# ma_esquema.net
KiCad netlist of a schematic drawn in EAGLE
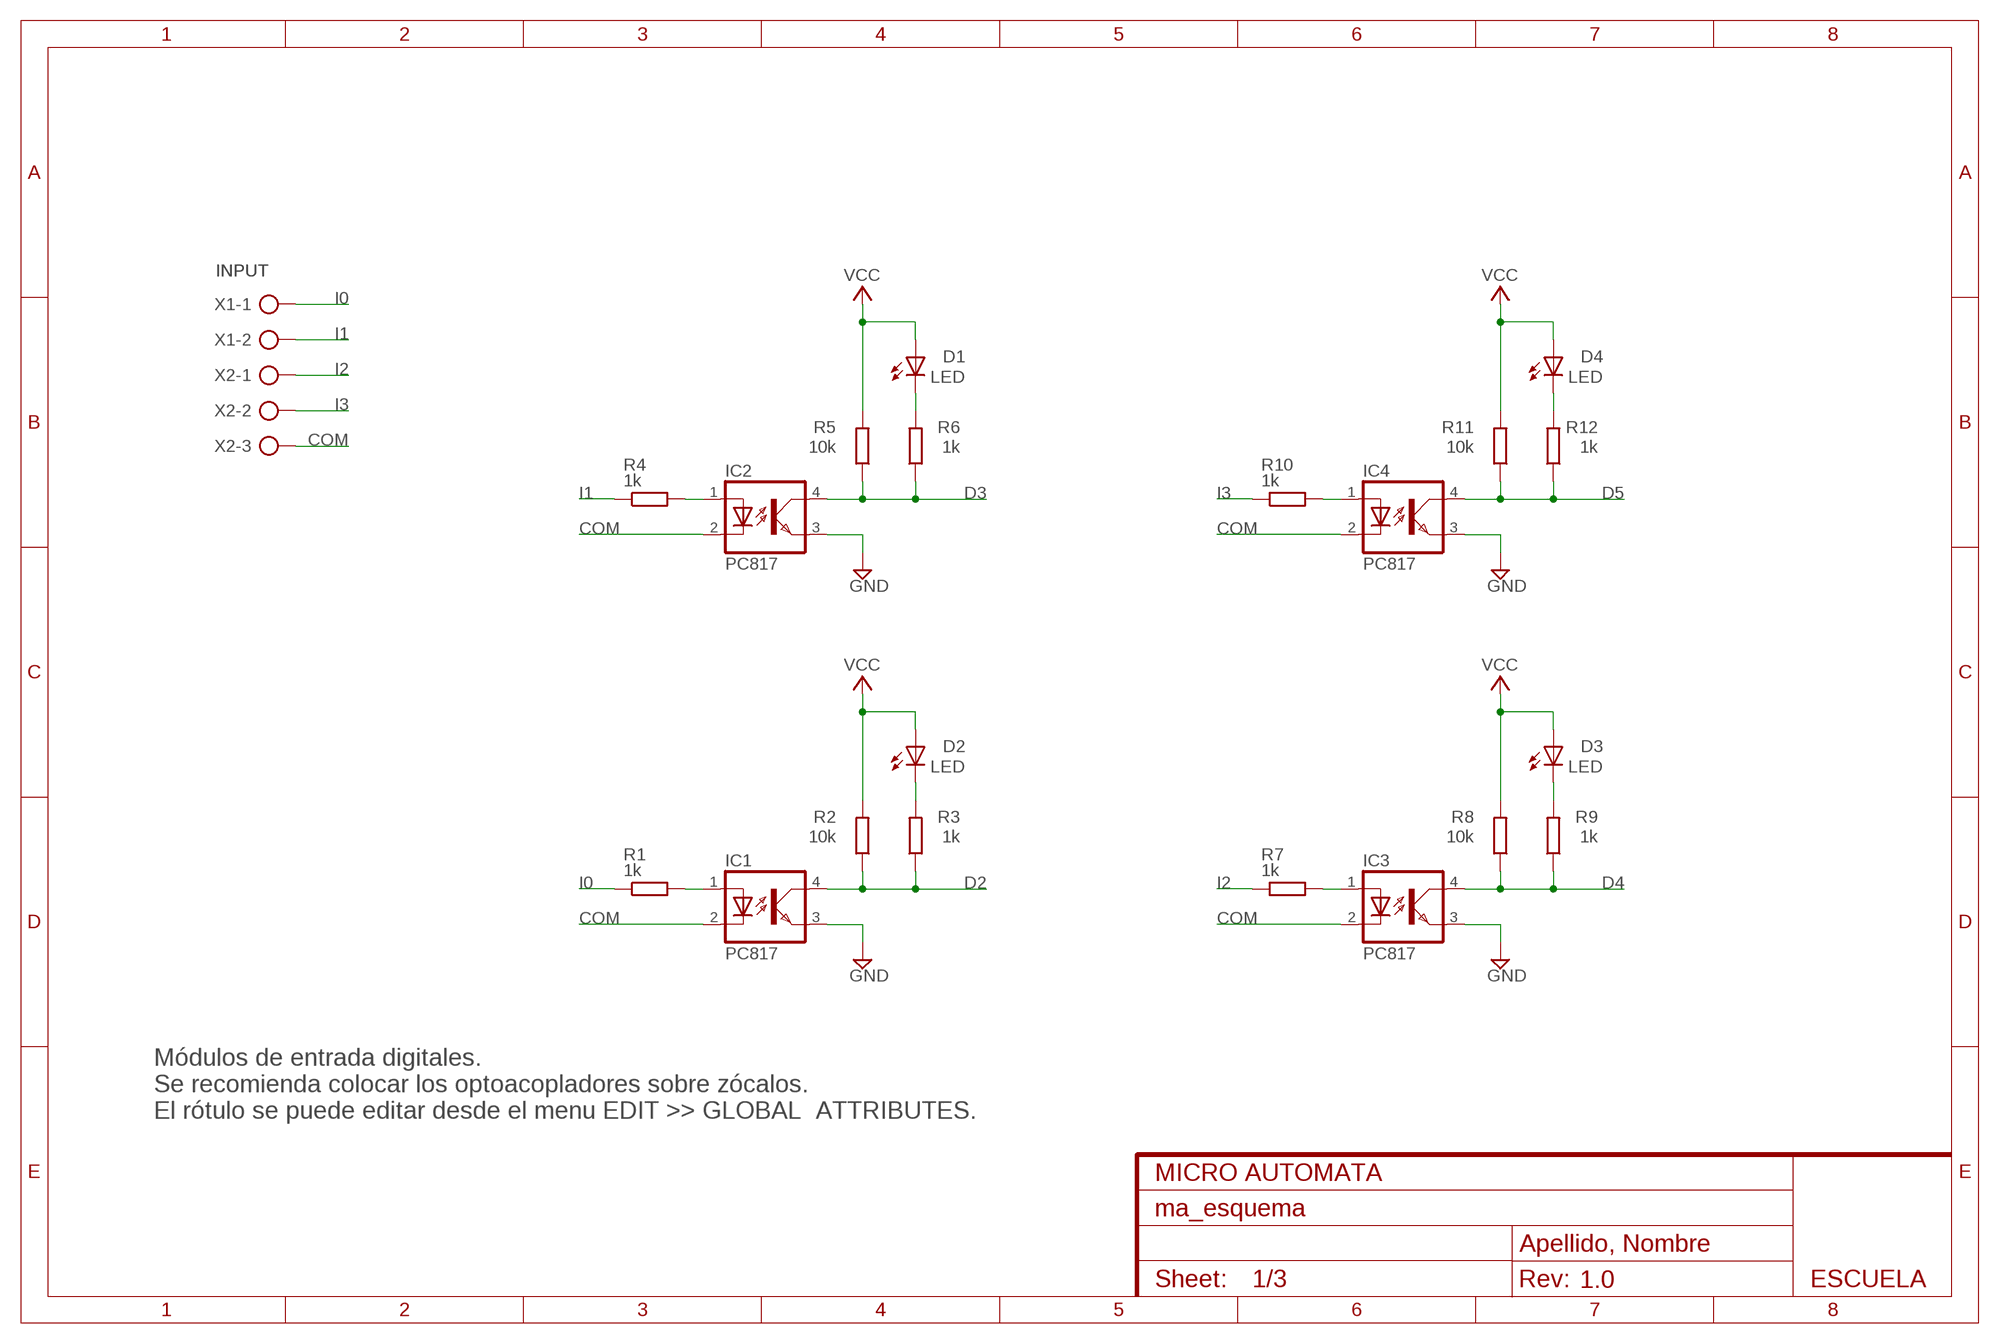
[diagram p0: schematic, sheet 1]
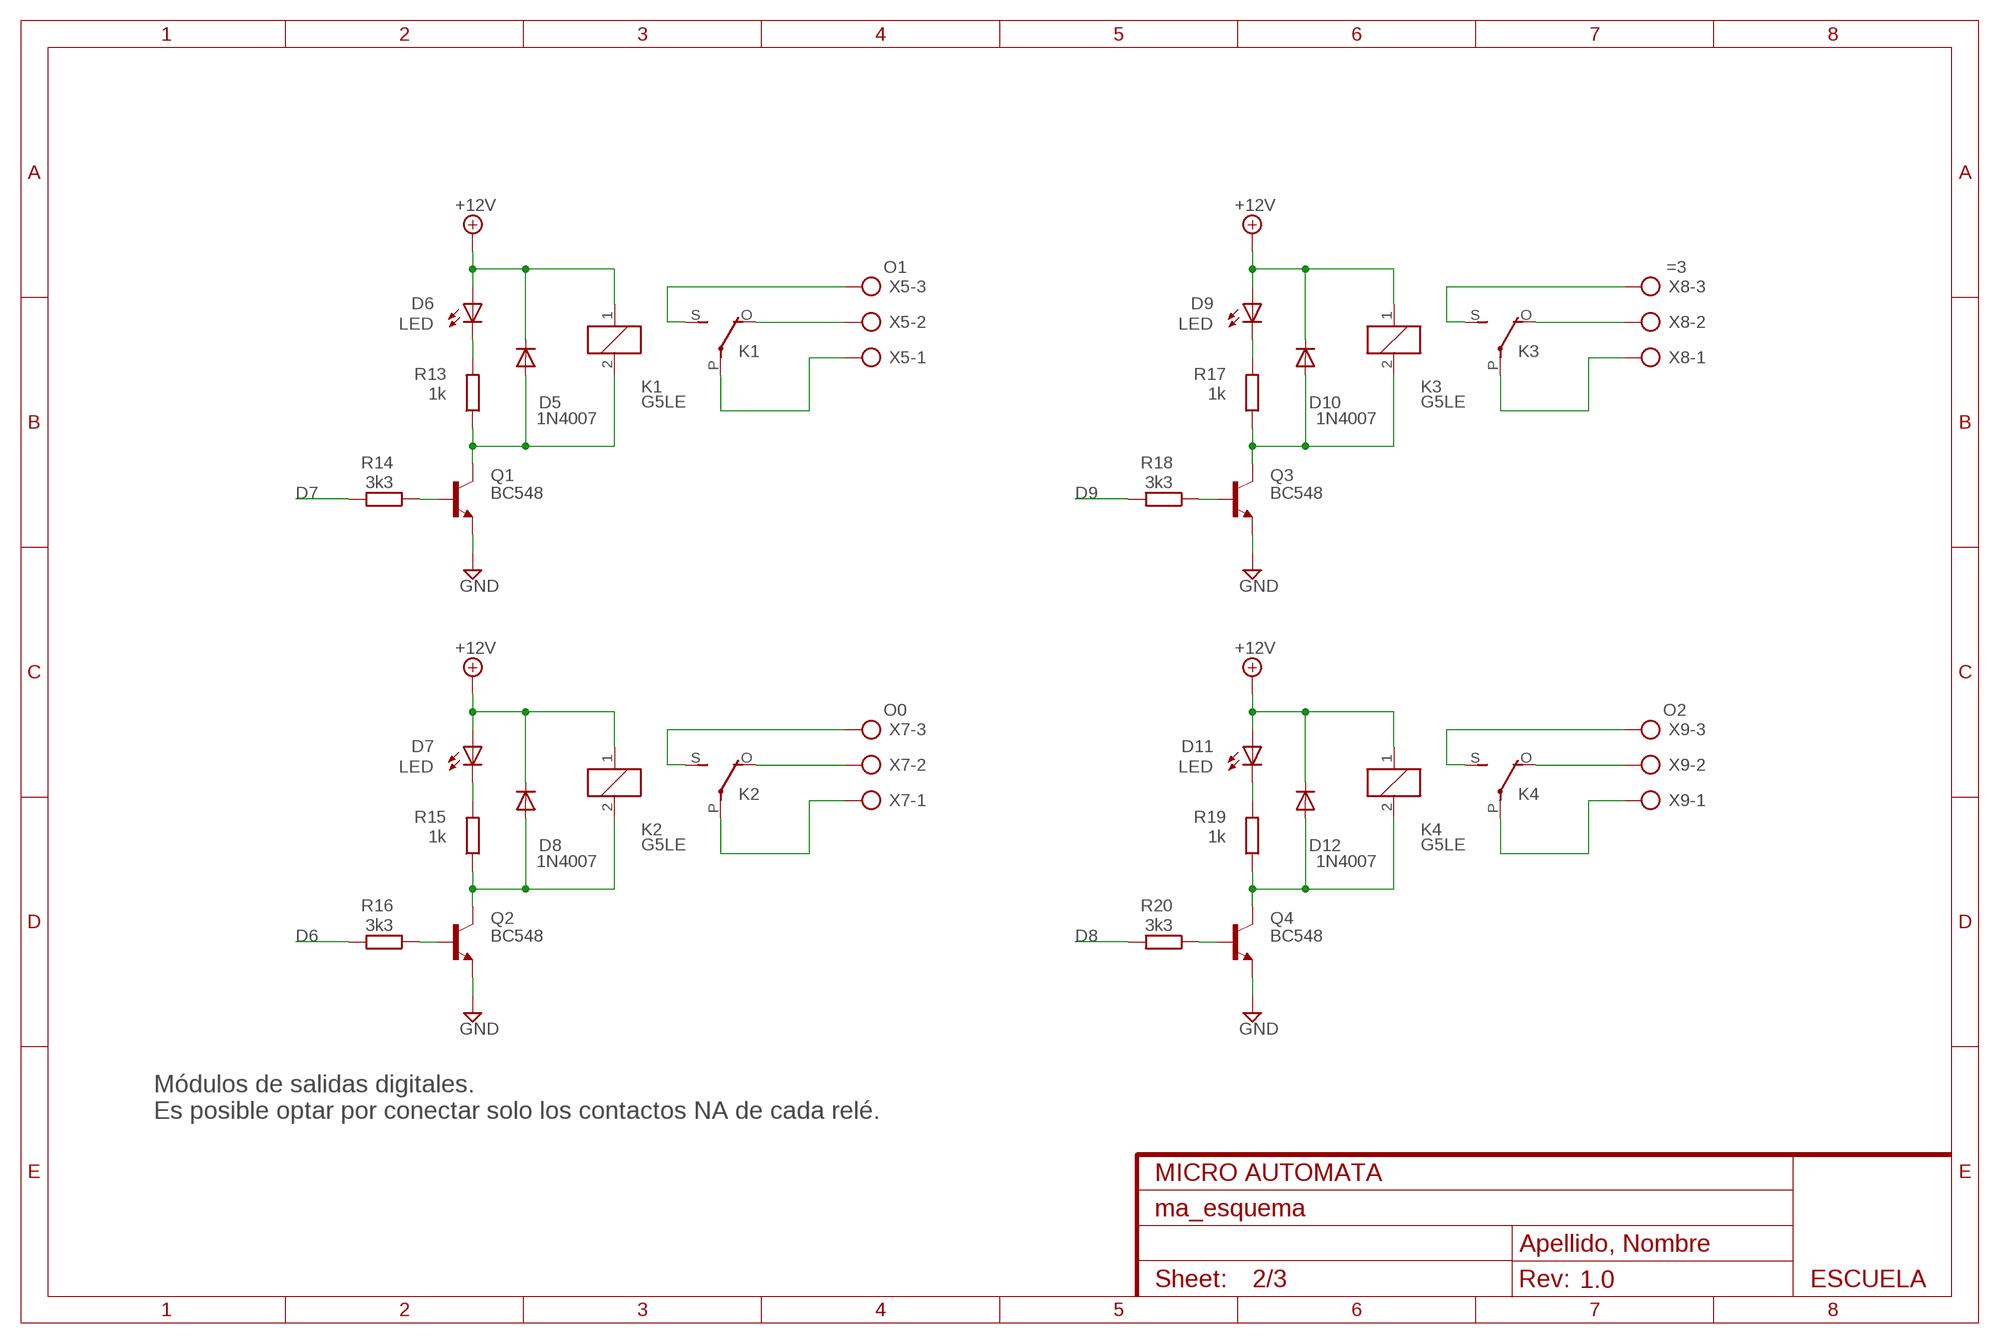
[diagram p1: schematic, sheet 2]
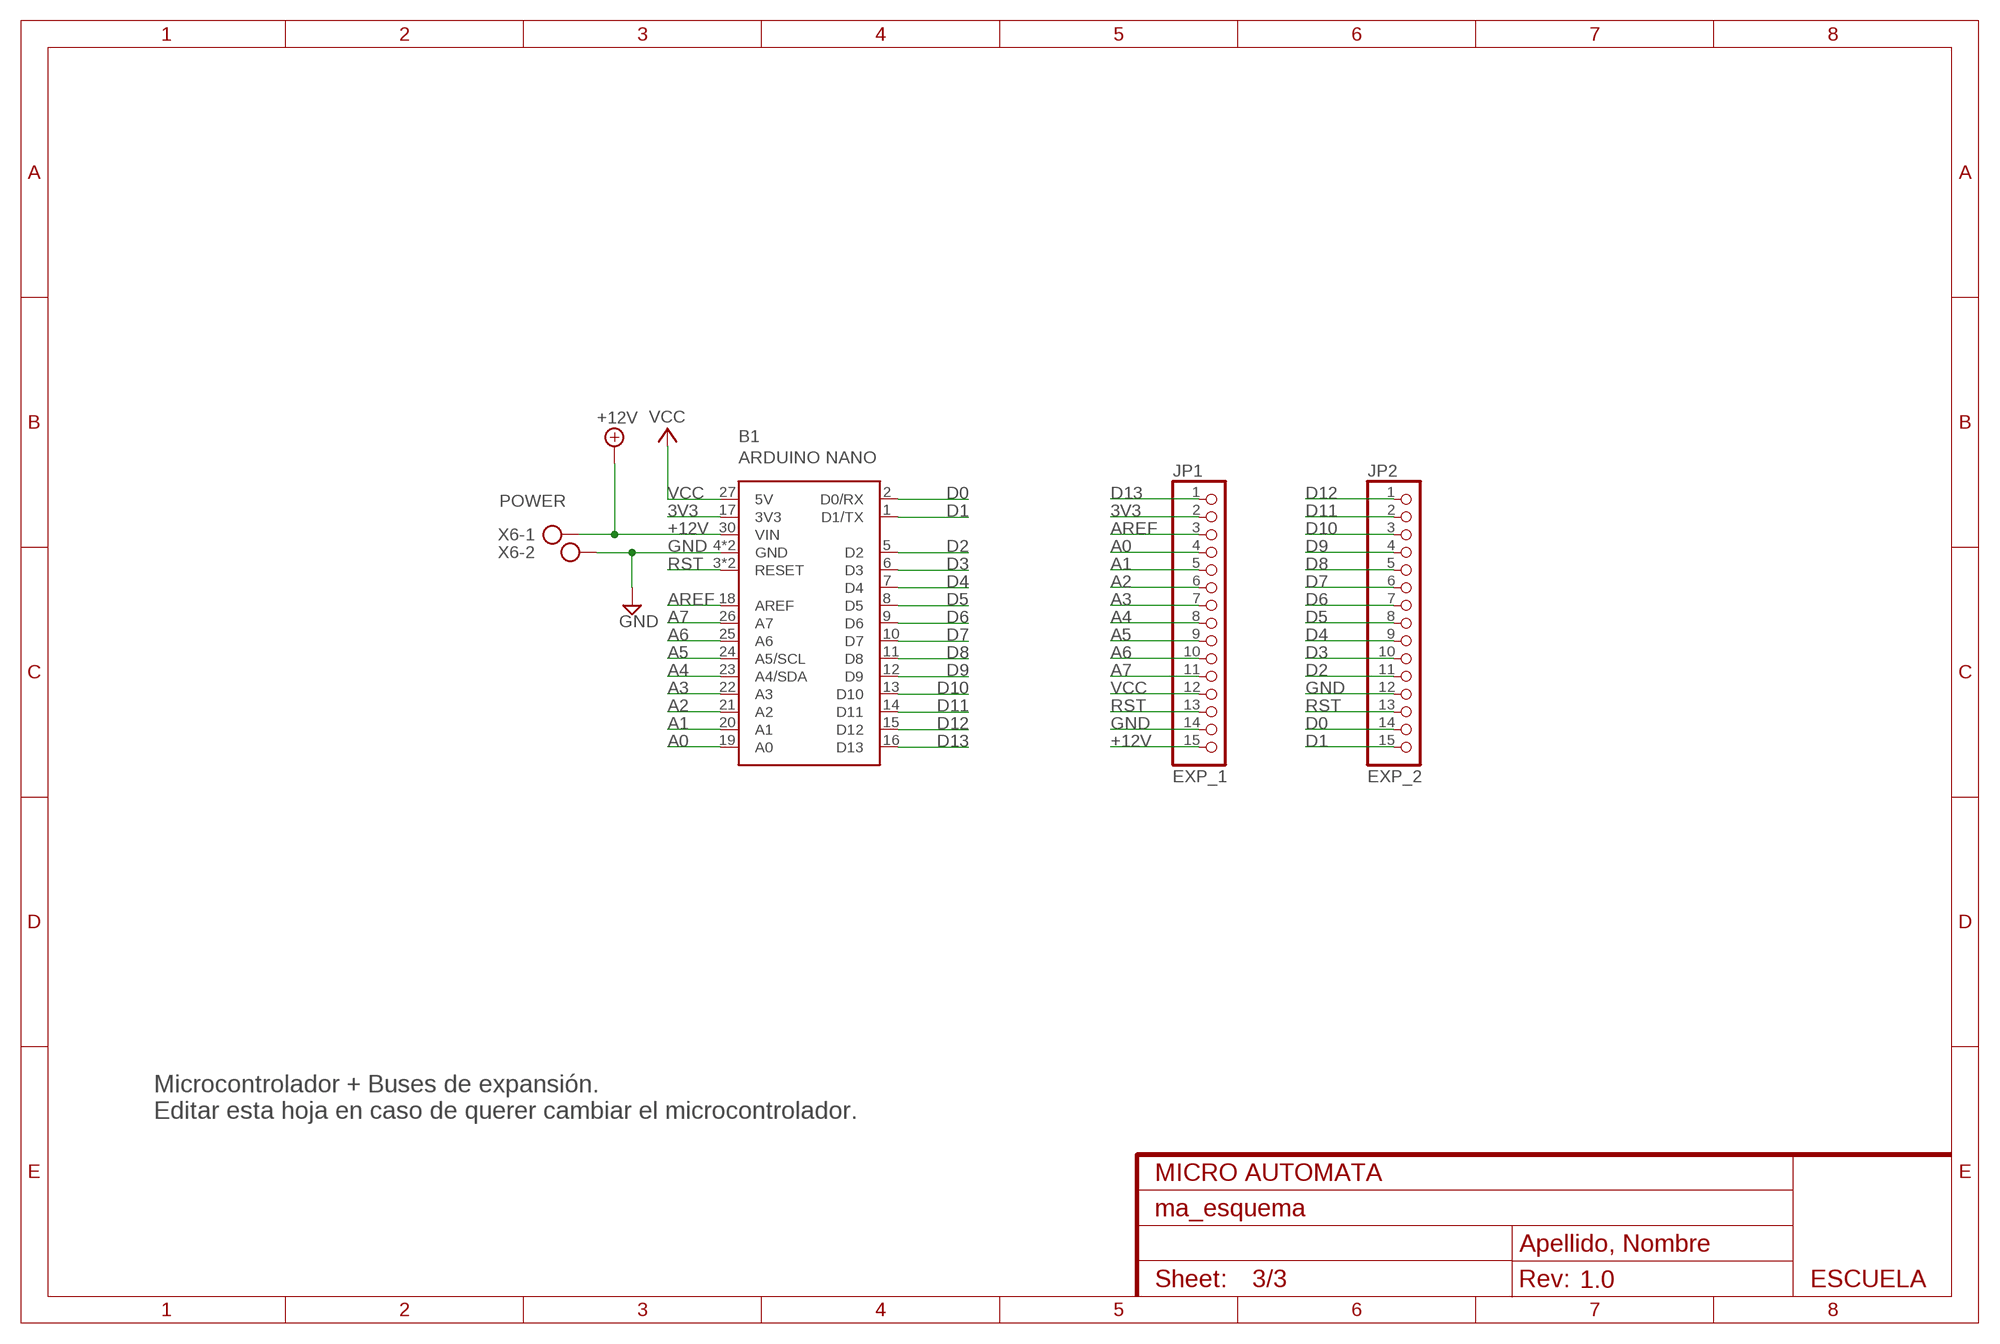
[diagram p2: schematic, sheet 3]

(export (version "E")
  (design (tool "Eeschema 10.0.6"))
  (components
    (comp (ref "B1")
      (value "ARDUINO NANO")
      (footprint "eagle-import:NANO")
      (libsource (lib "eagle-import") (part "ARDUINO_NANO"))
    )
    (comp (ref "JP1")
      (value "EXP_1")
      (footprint "eagle-import:1X15")
      (libsource (lib "eagle-import") (part "PINHD-1X15"))
    )
    (comp (ref "JP2")
      (value "EXP_2")
      (footprint "eagle-import:1X15")
      (libsource (lib "eagle-import") (part "PINHD-1X15"))
    )
    (comp (ref "X6")
      (value "POWER")
      (footprint "eagle-import:AK500_2")
      (libsource (lib "eagle-import") (part "BORNERA_AK500/2"))
    )
    (comp (ref "D1")
      (value "LED")
      (footprint "eagle-import:LED_3MM")
      (libsource (lib "eagle-import") (part "LED3MM"))
    )
    (comp (ref "D2")
      (value "LED")
      (footprint "eagle-import:LED_3MM")
      (libsource (lib "eagle-import") (part "LED3MM"))
    )
    (comp (ref "D3")
      (value "LED")
      (footprint "eagle-import:LED_3MM")
      (libsource (lib "eagle-import") (part "LED3MM"))
    )
    (comp (ref "D4")
      (value "LED")
      (footprint "eagle-import:LED_3MM")
      (libsource (lib "eagle-import") (part "LED3MM"))
    )
    (comp (ref "IC1")
      (value "PC817")
      (footprint "eagle-import:DIL04")
      (fields (field (name "MPN") "PC817X4J000F"))
      (libsource (lib "eagle-import") (part "PC817"))
    )
    (comp (ref "IC2")
      (value "PC817")
      (footprint "eagle-import:DIL04")
      (fields (field (name "MPN") "PC817X4J000F"))
      (libsource (lib "eagle-import") (part "PC817"))
    )
    (comp (ref "IC3")
      (value "PC817")
      (footprint "eagle-import:DIL04")
      (fields (field (name "MPN") "PC817X4J000F"))
      (libsource (lib "eagle-import") (part "PC817"))
    )
    (comp (ref "IC4")
      (value "PC817")
      (footprint "eagle-import:DIL04")
      (fields (field (name "MPN") "PC817X4J000F"))
      (libsource (lib "eagle-import") (part "PC817"))
    )
    (comp (ref "R1")
      (value "1k")
      (footprint "eagle-import:0204_7")
      (libsource (lib "eagle-import") (part "RESISTOR-EU0204/7"))
    )
    (comp (ref "R2")
      (value "10k")
      (footprint "eagle-import:0204_7")
      (libsource (lib "eagle-import") (part "RESISTOR-EU0204/7"))
    )
    (comp (ref "R3")
      (value "1k")
      (footprint "eagle-import:0204_7")
      (libsource (lib "eagle-import") (part "RESISTOR-EU0204/7"))
    )
    (comp (ref "R4")
      (value "1k")
      (footprint "eagle-import:0204_7")
      (libsource (lib "eagle-import") (part "RESISTOR-EU0204/7"))
    )
    (comp (ref "R5")
      (value "10k")
      (footprint "eagle-import:0204_7")
      (libsource (lib "eagle-import") (part "RESISTOR-EU0204/7"))
    )
    (comp (ref "R6")
      (value "1k")
      (footprint "eagle-import:0204_7")
      (libsource (lib "eagle-import") (part "RESISTOR-EU0204/7"))
    )
    (comp (ref "R7")
      (value "1k")
      (footprint "eagle-import:0204_7")
      (libsource (lib "eagle-import") (part "RESISTOR-EU0204/7"))
    )
    (comp (ref "R8")
      (value "10k")
      (footprint "eagle-import:0204_7")
      (libsource (lib "eagle-import") (part "RESISTOR-EU0204/7"))
    )
    (comp (ref "R9")
      (value "1k")
      (footprint "eagle-import:0204_7")
      (libsource (lib "eagle-import") (part "RESISTOR-EU0204/7"))
    )
    (comp (ref "R10")
      (value "1k")
      (footprint "eagle-import:0204_7")
      (libsource (lib "eagle-import") (part "RESISTOR-EU0204/7"))
    )
    (comp (ref "R11")
      (value "10k")
      (footprint "eagle-import:0204_7")
      (libsource (lib "eagle-import") (part "RESISTOR-EU0204/7"))
    )
    (comp (ref "R12")
      (value "1k")
      (footprint "eagle-import:0204_7")
      (libsource (lib "eagle-import") (part "RESISTOR-EU0204/7"))
    )
    (comp (ref "X1")
      (value "INPUT")
      (footprint "eagle-import:AK500_2")
      (libsource (lib "eagle-import") (part "BORNERA_AK500/2"))
    )
    (comp (ref "X2")
      (value "INPUT")
      (footprint "eagle-import:AK500_3")
      (libsource (lib "eagle-import") (part "BORNERA_AK500/3"))
    )
    (comp (ref "D5")
      (value "1N4007")
      (footprint "eagle-import:DO41-10")
      (libsource (lib "eagle-import") (part "1N4007"))
    )
    (comp (ref "D6")
      (value "LED")
      (footprint "eagle-import:LED_3MM")
      (libsource (lib "eagle-import") (part "LED3MM"))
    )
    (comp (ref "D7")
      (value "LED")
      (footprint "eagle-import:LED_3MM")
      (libsource (lib "eagle-import") (part "LED3MM"))
    )
    (comp (ref "D8")
      (value "1N4007")
      (footprint "eagle-import:DO41-10")
      (libsource (lib "eagle-import") (part "1N4007"))
    )
    (comp (ref "D9")
      (value "LED")
      (footprint "eagle-import:LED_3MM")
      (libsource (lib "eagle-import") (part "LED3MM"))
    )
    (comp (ref "D10")
      (value "1N4007")
      (footprint "eagle-import:DO41-10")
      (libsource (lib "eagle-import") (part "1N4007"))
    )
    (comp (ref "D11")
      (value "LED")
      (footprint "eagle-import:LED_3MM")
      (libsource (lib "eagle-import") (part "LED3MM"))
    )
    (comp (ref "D12")
      (value "1N4007")
      (footprint "eagle-import:DO41-10")
      (libsource (lib "eagle-import") (part "1N4007"))
    )
    (comp (ref "K1")
      (value "G5LE")
      (footprint "eagle-import:G5LE")
      (libsource (lib "eagle-import") (part "RELE_G5LE"))
    )
    (comp (ref "K2")
      (value "G5LE")
      (footprint "eagle-import:G5LE")
      (libsource (lib "eagle-import") (part "RELE_G5LE"))
    )
    (comp (ref "K3")
      (value "G5LE")
      (footprint "eagle-import:G5LE")
      (libsource (lib "eagle-import") (part "RELE_G5LE"))
    )
    (comp (ref "K4")
      (value "G5LE")
      (footprint "eagle-import:G5LE")
      (libsource (lib "eagle-import") (part "RELE_G5LE"))
    )
    (comp (ref "Q1")
      (value "BC548")
      (footprint "eagle-import:TO92-EBC")
      (libsource (lib "eagle-import") (part "BC548"))
    )
    (comp (ref "Q2")
      (value "BC548")
      (footprint "eagle-import:TO92-EBC")
      (libsource (lib "eagle-import") (part "BC548"))
    )
    (comp (ref "Q3")
      (value "BC548")
      (footprint "eagle-import:TO92-EBC")
      (libsource (lib "eagle-import") (part "BC548"))
    )
    (comp (ref "Q4")
      (value "BC548")
      (footprint "eagle-import:TO92-EBC")
      (libsource (lib "eagle-import") (part "BC548"))
    )
    (comp (ref "R13")
      (value "1k")
      (footprint "eagle-import:0204_7")
      (libsource (lib "eagle-import") (part "RESISTOR-EU0204/7"))
    )
    (comp (ref "R14")
      (value "3k3")
      (footprint "eagle-import:0204_7")
      (libsource (lib "eagle-import") (part "RESISTOR-EU0204/7"))
    )
    (comp (ref "R15")
      (value "1k")
      (footprint "eagle-import:0204_7")
      (libsource (lib "eagle-import") (part "RESISTOR-EU0204/7"))
    )
    (comp (ref "R16")
      (value "3k3")
      (footprint "eagle-import:0204_7")
      (libsource (lib "eagle-import") (part "RESISTOR-EU0204/7"))
    )
    (comp (ref "R17")
      (value "1k")
      (footprint "eagle-import:0204_7")
      (libsource (lib "eagle-import") (part "RESISTOR-EU0204/7"))
    )
    (comp (ref "R18")
      (value "3k3")
      (footprint "eagle-import:0204_7")
      (libsource (lib "eagle-import") (part "RESISTOR-EU0204/7"))
    )
    (comp (ref "R19")
      (value "1k")
      (footprint "eagle-import:0204_7")
      (libsource (lib "eagle-import") (part "RESISTOR-EU0204/7"))
    )
    (comp (ref "R20")
      (value "3k3")
      (footprint "eagle-import:0204_7")
      (libsource (lib "eagle-import") (part "RESISTOR-EU0204/7"))
    )
    (comp (ref "X5")
      (value "O1")
      (footprint "eagle-import:AK500_3")
      (libsource (lib "eagle-import") (part "BORNERA_AK500/3"))
    )
    (comp (ref "X7")
      (value "O0")
      (footprint "eagle-import:AK500_3")
      (libsource (lib "eagle-import") (part "BORNERA_AK500/3"))
    )
    (comp (ref "X8")
      (value "=3")
      (footprint "eagle-import:AK500_3")
      (libsource (lib "eagle-import") (part "BORNERA_AK500/3"))
    )
    (comp (ref "X9")
      (value "O2")
      (footprint "eagle-import:AK500_3")
      (libsource (lib "eagle-import") (part "BORNERA_AK500/3"))
    )
  )
  (nets
    (net (code "1") (name "+12V") (class "Default")
      (node (ref "B1") (pin "30") (pinfunction "VIN_30") (pintype "bidirectional"))
      (node (ref "D10") (pin "C") (pinfunction "C_C") (pintype "passive"))
      (node (ref "D11") (pin "A") (pinfunction "A_A") (pintype "passive"))
      (node (ref "D12") (pin "C") (pinfunction "C_C") (pintype "passive"))
      (node (ref "D5") (pin "C") (pinfunction "C_C") (pintype "passive"))
      (node (ref "D6") (pin "A") (pinfunction "A_A") (pintype "passive"))
      (node (ref "D7") (pin "A") (pinfunction "A_A") (pintype "passive"))
      (node (ref "D8") (pin "C") (pinfunction "C_C") (pintype "passive"))
      (node (ref "D9") (pin "A") (pinfunction "A_A") (pintype "passive"))
      (node (ref "JP1") (pin "15") (pinfunction "15_15") (pintype "passive"))
      (node (ref "K1") (pin "1") (pinfunction "1_1") (pintype "passive"))
      (node (ref "K2") (pin "1") (pinfunction "1_1") (pintype "passive"))
      (node (ref "K3") (pin "1") (pinfunction "1_1") (pintype "passive"))
      (node (ref "K4") (pin "1") (pinfunction "1_1") (pintype "passive"))
      (node (ref "X6") (pin "1") (pinfunction "KL_1") (pintype "passive"))
    )
    (net (code "2") (name "3V3") (class "Default")
      (node (ref "B1") (pin "17") (pinfunction "3V3_17") (pintype "bidirectional"))
      (node (ref "JP1") (pin "2") (pinfunction "2_2") (pintype "passive"))
    )
    (net (code "3") (name "A0") (class "Default")
      (node (ref "B1") (pin "19") (pinfunction "A0_19") (pintype "bidirectional"))
      (node (ref "JP1") (pin "4") (pinfunction "4_4") (pintype "passive"))
    )
    (net (code "4") (name "A1") (class "Default")
      (node (ref "B1") (pin "20") (pinfunction "A1_20") (pintype "bidirectional"))
      (node (ref "JP1") (pin "5") (pinfunction "5_5") (pintype "passive"))
    )
    (net (code "5") (name "A2") (class "Default")
      (node (ref "B1") (pin "21") (pinfunction "A2_21") (pintype "bidirectional"))
      (node (ref "JP1") (pin "6") (pinfunction "6_6") (pintype "passive"))
    )
    (net (code "6") (name "A3") (class "Default")
      (node (ref "B1") (pin "22") (pinfunction "A3_22") (pintype "bidirectional"))
      (node (ref "JP1") (pin "7") (pinfunction "7_7") (pintype "passive"))
    )
    (net (code "7") (name "A4") (class "Default")
      (node (ref "B1") (pin "23") (pinfunction "A4/SDA_23") (pintype "bidirectional"))
      (node (ref "JP1") (pin "8") (pinfunction "8_8") (pintype "passive"))
    )
    (net (code "8") (name "A5") (class "Default")
      (node (ref "B1") (pin "24") (pinfunction "A5/SCL_24") (pintype "bidirectional"))
      (node (ref "JP1") (pin "9") (pinfunction "9_9") (pintype "passive"))
    )
    (net (code "9") (name "A6") (class "Default")
      (node (ref "B1") (pin "25") (pinfunction "A6_25") (pintype "bidirectional"))
      (node (ref "JP1") (pin "10") (pinfunction "10_10") (pintype "passive"))
    )
    (net (code "10") (name "A7") (class "Default")
      (node (ref "B1") (pin "26") (pinfunction "A7_26") (pintype "bidirectional"))
      (node (ref "JP1") (pin "11") (pinfunction "11_11") (pintype "passive"))
    )
    (net (code "11") (name "AREF") (class "Default")
      (node (ref "B1") (pin "18") (pinfunction "AREF_18") (pintype "bidirectional"))
      (node (ref "JP1") (pin "3") (pinfunction "3_3") (pintype "passive"))
    )
    (net (code "12") (name "COM") (class "Default")
      (node (ref "IC1") (pin "2") (pinfunction "C_2") (pintype "passive"))
      (node (ref "IC2") (pin "2") (pinfunction "C_2") (pintype "passive"))
      (node (ref "IC3") (pin "2") (pinfunction "C_2") (pintype "passive"))
      (node (ref "IC4") (pin "2") (pinfunction "C_2") (pintype "passive"))
      (node (ref "X2") (pin "3") (pinfunction "KL_3") (pintype "passive"))
    )
    (net (code "13") (name "D0") (class "Default")
      (node (ref "B1") (pin "2") (pinfunction "D0/RX_2") (pintype "bidirectional"))
      (node (ref "JP2") (pin "14") (pinfunction "14_14") (pintype "passive"))
    )
    (net (code "14") (name "D1") (class "Default")
      (node (ref "B1") (pin "1") (pinfunction "D1/TX_1") (pintype "bidirectional"))
      (node (ref "JP2") (pin "15") (pinfunction "15_15") (pintype "passive"))
    )
    (net (code "15") (name "D2") (class "Default")
      (node (ref "B1") (pin "5") (pinfunction "D2_5") (pintype "bidirectional"))
      (node (ref "IC1") (pin "4") (pinfunction "COL_4") (pintype "passive"))
      (node (ref "JP2") (pin "11") (pinfunction "11_11") (pintype "passive"))
      (node (ref "R2") (pin "1") (pinfunction "1_1") (pintype "passive"))
      (node (ref "R3") (pin "1") (pinfunction "1_1") (pintype "passive"))
    )
    (net (code "16") (name "D3") (class "Default")
      (node (ref "B1") (pin "6") (pinfunction "D3_6") (pintype "bidirectional"))
      (node (ref "IC2") (pin "4") (pinfunction "COL_4") (pintype "passive"))
      (node (ref "JP2") (pin "10") (pinfunction "10_10") (pintype "passive"))
      (node (ref "R5") (pin "1") (pinfunction "1_1") (pintype "passive"))
      (node (ref "R6") (pin "1") (pinfunction "1_1") (pintype "passive"))
    )
    (net (code "17") (name "D4") (class "Default")
      (node (ref "B1") (pin "7") (pinfunction "D4_7") (pintype "bidirectional"))
      (node (ref "IC3") (pin "4") (pinfunction "COL_4") (pintype "passive"))
      (node (ref "JP2") (pin "9") (pinfunction "9_9") (pintype "passive"))
      (node (ref "R8") (pin "1") (pinfunction "1_1") (pintype "passive"))
      (node (ref "R9") (pin "1") (pinfunction "1_1") (pintype "passive"))
    )
    (net (code "18") (name "D5") (class "Default")
      (node (ref "B1") (pin "8") (pinfunction "D5_8") (pintype "bidirectional"))
      (node (ref "IC4") (pin "4") (pinfunction "COL_4") (pintype "passive"))
      (node (ref "JP2") (pin "8") (pinfunction "8_8") (pintype "passive"))
      (node (ref "R11") (pin "1") (pinfunction "1_1") (pintype "passive"))
      (node (ref "R12") (pin "1") (pinfunction "1_1") (pintype "passive"))
    )
    (net (code "19") (name "D6") (class "Default")
      (node (ref "B1") (pin "9") (pinfunction "D6_9") (pintype "bidirectional"))
      (node (ref "JP2") (pin "7") (pinfunction "7_7") (pintype "passive"))
      (node (ref "R16") (pin "2") (pinfunction "2_2") (pintype "passive"))
    )
    (net (code "20") (name "D7") (class "Default")
      (node (ref "B1") (pin "10") (pinfunction "D7_10") (pintype "bidirectional"))
      (node (ref "JP2") (pin "6") (pinfunction "6_6") (pintype "passive"))
      (node (ref "R14") (pin "2") (pinfunction "2_2") (pintype "passive"))
    )
    (net (code "21") (name "D8") (class "Default")
      (node (ref "B1") (pin "11") (pinfunction "D8_11") (pintype "bidirectional"))
      (node (ref "JP2") (pin "5") (pinfunction "5_5") (pintype "passive"))
      (node (ref "R20") (pin "2") (pinfunction "2_2") (pintype "passive"))
    )
    (net (code "22") (name "D9") (class "Default")
      (node (ref "B1") (pin "12") (pinfunction "D9_12") (pintype "bidirectional"))
      (node (ref "JP2") (pin "4") (pinfunction "4_4") (pintype "passive"))
      (node (ref "R18") (pin "2") (pinfunction "2_2") (pintype "passive"))
    )
    (net (code "23") (name "D10") (class "Default")
      (node (ref "B1") (pin "13") (pinfunction "D10_13") (pintype "bidirectional"))
      (node (ref "JP2") (pin "3") (pinfunction "3_3") (pintype "passive"))
    )
    (net (code "24") (name "D11") (class "Default")
      (node (ref "B1") (pin "14") (pinfunction "D11_14") (pintype "bidirectional"))
      (node (ref "JP2") (pin "2") (pinfunction "2_2") (pintype "passive"))
    )
    (net (code "25") (name "D12") (class "Default")
      (node (ref "B1") (pin "15") (pinfunction "D12_15") (pintype "bidirectional"))
      (node (ref "JP2") (pin "1") (pinfunction "1_1") (pintype "passive"))
    )
    (net (code "26") (name "D13") (class "Default")
      (node (ref "B1") (pin "16") (pinfunction "D13_16") (pintype "bidirectional"))
      (node (ref "JP1") (pin "1") (pinfunction "1_1") (pintype "passive"))
    )
    (net (code "27") (name "GND") (class "Default")
      (node (ref "B1") (pin "29") (pinfunction "GND_29") (pintype "bidirectional"))
      (node (ref "B1") (pin "4") (pinfunction "GND_4") (pintype "bidirectional"))
      (node (ref "IC1") (pin "3") (pinfunction "EMIT_3") (pintype "passive"))
      (node (ref "IC2") (pin "3") (pinfunction "EMIT_3") (pintype "passive"))
      (node (ref "IC3") (pin "3") (pinfunction "EMIT_3") (pintype "passive"))
      (node (ref "IC4") (pin "3") (pinfunction "EMIT_3") (pintype "passive"))
      (node (ref "JP1") (pin "14") (pinfunction "14_14") (pintype "passive"))
      (node (ref "JP2") (pin "12") (pinfunction "12_12") (pintype "passive"))
      (node (ref "Q1") (pin "E") (pinfunction "E_E") (pintype "passive"))
      (node (ref "Q2") (pin "E") (pinfunction "E_E") (pintype "passive"))
      (node (ref "Q3") (pin "E") (pinfunction "E_E") (pintype "passive"))
      (node (ref "Q4") (pin "E") (pinfunction "E_E") (pintype "passive"))
      (node (ref "X6") (pin "2") (pinfunction "KL_2") (pintype "passive"))
    )
    (net (code "28") (name "I0") (class "Default")
      (node (ref "R1") (pin "1") (pinfunction "1_1") (pintype "passive"))
      (node (ref "X1") (pin "1") (pinfunction "KL_1") (pintype "passive"))
    )
    (net (code "29") (name "I1") (class "Default")
      (node (ref "R4") (pin "1") (pinfunction "1_1") (pintype "passive"))
      (node (ref "X1") (pin "2") (pinfunction "KL_2") (pintype "passive"))
    )
    (net (code "30") (name "I2") (class "Default")
      (node (ref "R7") (pin "1") (pinfunction "1_1") (pintype "passive"))
      (node (ref "X2") (pin "1") (pinfunction "KL_1") (pintype "passive"))
    )
    (net (code "31") (name "I3") (class "Default")
      (node (ref "R10") (pin "1") (pinfunction "1_1") (pintype "passive"))
      (node (ref "X2") (pin "2") (pinfunction "KL_2") (pintype "passive"))
    )
    (net (code "32") (name "Net-(D1-C)") (class "Default")
      (node (ref "D1") (pin "K") (pinfunction "C_K") (pintype "passive"))
      (node (ref "R6") (pin "2") (pinfunction "2_2") (pintype "passive"))
    )
    (net (code "33") (name "Net-(D2-C)") (class "Default")
      (node (ref "D2") (pin "K") (pinfunction "C_K") (pintype "passive"))
      (node (ref "R3") (pin "2") (pinfunction "2_2") (pintype "passive"))
    )
    (net (code "34") (name "Net-(D3-C)") (class "Default")
      (node (ref "D3") (pin "K") (pinfunction "C_K") (pintype "passive"))
      (node (ref "R9") (pin "2") (pinfunction "2_2") (pintype "passive"))
    )
    (net (code "35") (name "Net-(D4-C)") (class "Default")
      (node (ref "D4") (pin "K") (pinfunction "C_K") (pintype "passive"))
      (node (ref "R12") (pin "2") (pinfunction "2_2") (pintype "passive"))
    )
    (net (code "36") (name "Net-(D5-PadA)") (class "Default")
      (node (ref "D5") (pin "A") (pinfunction "A_A") (pintype "passive"))
      (node (ref "K1") (pin "2") (pinfunction "2_2") (pintype "passive"))
      (node (ref "Q1") (pin "C") (pinfunction "C_C") (pintype "passive"))
      (node (ref "R13") (pin "1") (pinfunction "1_1") (pintype "passive"))
    )
    (net (code "37") (name "Net-(D6-C)") (class "Default")
      (node (ref "D6") (pin "K") (pinfunction "C_K") (pintype "passive"))
      (node (ref "R13") (pin "2") (pinfunction "2_2") (pintype "passive"))
    )
    (net (code "38") (name "Net-(D7-C)") (class "Default")
      (node (ref "D7") (pin "K") (pinfunction "C_K") (pintype "passive"))
      (node (ref "R15") (pin "2") (pinfunction "2_2") (pintype "passive"))
    )
    (net (code "39") (name "Net-(D8-PadA)") (class "Default")
      (node (ref "D8") (pin "A") (pinfunction "A_A") (pintype "passive"))
      (node (ref "K2") (pin "2") (pinfunction "2_2") (pintype "passive"))
      (node (ref "Q2") (pin "C") (pinfunction "C_C") (pintype "passive"))
      (node (ref "R15") (pin "1") (pinfunction "1_1") (pintype "passive"))
    )
    (net (code "40") (name "Net-(D9-C)") (class "Default")
      (node (ref "D9") (pin "K") (pinfunction "C_K") (pintype "passive"))
      (node (ref "R17") (pin "2") (pinfunction "2_2") (pintype "passive"))
    )
    (net (code "41") (name "Net-(D10-PadA)") (class "Default")
      (node (ref "D10") (pin "A") (pinfunction "A_A") (pintype "passive"))
      (node (ref "K3") (pin "2") (pinfunction "2_2") (pintype "passive"))
      (node (ref "Q3") (pin "C") (pinfunction "C_C") (pintype "passive"))
      (node (ref "R17") (pin "1") (pinfunction "1_1") (pintype "passive"))
    )
    (net (code "42") (name "Net-(D11-C)") (class "Default")
      (node (ref "D11") (pin "K") (pinfunction "C_K") (pintype "passive"))
      (node (ref "R19") (pin "2") (pinfunction "2_2") (pintype "passive"))
    )
    (net (code "43") (name "Net-(D12-PadA)") (class "Default")
      (node (ref "D12") (pin "A") (pinfunction "A_A") (pintype "passive"))
      (node (ref "K4") (pin "2") (pinfunction "2_2") (pintype "passive"))
      (node (ref "Q4") (pin "C") (pinfunction "C_C") (pintype "passive"))
      (node (ref "R19") (pin "1") (pinfunction "1_1") (pintype "passive"))
    )
    (net (code "44") (name "Net-(IC1-A)") (class "Default")
      (node (ref "IC1") (pin "1") (pinfunction "A_1") (pintype "passive"))
      (node (ref "R1") (pin "2") (pinfunction "2_2") (pintype "passive"))
    )
    (net (code "45") (name "Net-(IC2-A)") (class "Default")
      (node (ref "IC2") (pin "1") (pinfunction "A_1") (pintype "passive"))
      (node (ref "R4") (pin "2") (pinfunction "2_2") (pintype "passive"))
    )
    (net (code "46") (name "Net-(IC3-A)") (class "Default")
      (node (ref "IC3") (pin "1") (pinfunction "A_1") (pintype "passive"))
      (node (ref "R7") (pin "2") (pinfunction "2_2") (pintype "passive"))
    )
    (net (code "47") (name "Net-(IC4-A)") (class "Default")
      (node (ref "IC4") (pin "1") (pinfunction "A_1") (pintype "passive"))
      (node (ref "R10") (pin "2") (pinfunction "2_2") (pintype "passive"))
    )
    (net (code "48") (name "Net-(K1B-COM)") (class "Default")
      (node (ref "K1") (pin "P") (pinfunction "COM_P") (pintype "passive"))
      (node (ref "X5") (pin "1") (pinfunction "KL_1") (pintype "passive"))
    )
    (net (code "49") (name "Net-(K1B-NA)") (class "Default")
      (node (ref "K1") (pin "S") (pinfunction "NA_S") (pintype "passive"))
      (node (ref "X5") (pin "3") (pinfunction "KL_3") (pintype "passive"))
    )
    (net (code "50") (name "Net-(K1B-NC)") (class "Default")
      (node (ref "K1") (pin "O") (pinfunction "NC_O") (pintype "passive"))
      (node (ref "X5") (pin "2") (pinfunction "KL_2") (pintype "passive"))
    )
    (net (code "51") (name "Net-(K2B-COM)") (class "Default")
      (node (ref "K2") (pin "P") (pinfunction "COM_P") (pintype "passive"))
      (node (ref "X7") (pin "1") (pinfunction "KL_1") (pintype "passive"))
    )
    (net (code "52") (name "Net-(K2B-NA)") (class "Default")
      (node (ref "K2") (pin "S") (pinfunction "NA_S") (pintype "passive"))
      (node (ref "X7") (pin "3") (pinfunction "KL_3") (pintype "passive"))
    )
    (net (code "53") (name "Net-(K2B-NC)") (class "Default")
      (node (ref "K2") (pin "O") (pinfunction "NC_O") (pintype "passive"))
      (node (ref "X7") (pin "2") (pinfunction "KL_2") (pintype "passive"))
    )
    (net (code "54") (name "Net-(K3B-COM)") (class "Default")
      (node (ref "K3") (pin "P") (pinfunction "COM_P") (pintype "passive"))
      (node (ref "X8") (pin "1") (pinfunction "KL_1") (pintype "passive"))
    )
    (net (code "55") (name "Net-(K3B-NA)") (class "Default")
      (node (ref "K3") (pin "S") (pinfunction "NA_S") (pintype "passive"))
      (node (ref "X8") (pin "3") (pinfunction "KL_3") (pintype "passive"))
    )
    (net (code "56") (name "Net-(K3B-NC)") (class "Default")
      (node (ref "K3") (pin "O") (pinfunction "NC_O") (pintype "passive"))
      (node (ref "X8") (pin "2") (pinfunction "KL_2") (pintype "passive"))
    )
    (net (code "57") (name "Net-(K4B-COM)") (class "Default")
      (node (ref "K4") (pin "P") (pinfunction "COM_P") (pintype "passive"))
      (node (ref "X9") (pin "1") (pinfunction "KL_1") (pintype "passive"))
    )
    (net (code "58") (name "Net-(K4B-NA)") (class "Default")
      (node (ref "K4") (pin "S") (pinfunction "NA_S") (pintype "passive"))
      (node (ref "X9") (pin "3") (pinfunction "KL_3") (pintype "passive"))
    )
    (net (code "59") (name "Net-(K4B-NC)") (class "Default")
      (node (ref "K4") (pin "O") (pinfunction "NC_O") (pintype "passive"))
      (node (ref "X9") (pin "2") (pinfunction "KL_2") (pintype "passive"))
    )
    (net (code "60") (name "Net-(Q1-PadB)") (class "Default")
      (node (ref "Q1") (pin "B") (pinfunction "B_B") (pintype "passive"))
      (node (ref "R14") (pin "1") (pinfunction "1_1") (pintype "passive"))
    )
    (net (code "61") (name "Net-(Q2-PadB)") (class "Default")
      (node (ref "Q2") (pin "B") (pinfunction "B_B") (pintype "passive"))
      (node (ref "R16") (pin "1") (pinfunction "1_1") (pintype "passive"))
    )
    (net (code "62") (name "Net-(Q3-PadB)") (class "Default")
      (node (ref "Q3") (pin "B") (pinfunction "B_B") (pintype "passive"))
      (node (ref "R18") (pin "1") (pinfunction "1_1") (pintype "passive"))
    )
    (net (code "63") (name "Net-(Q4-PadB)") (class "Default")
      (node (ref "Q4") (pin "B") (pinfunction "B_B") (pintype "passive"))
      (node (ref "R20") (pin "1") (pinfunction "1_1") (pintype "passive"))
    )
    (net (code "64") (name "RST") (class "Default")
      (node (ref "B1") (pin "28") (pinfunction "RESET_28") (pintype "bidirectional"))
      (node (ref "B1") (pin "3") (pinfunction "RESET_3") (pintype "bidirectional"))
      (node (ref "JP1") (pin "13") (pinfunction "13_13") (pintype "passive"))
      (node (ref "JP2") (pin "13") (pinfunction "13_13") (pintype "passive"))
    )
    (net (code "65") (name "VCC") (class "Default")
      (node (ref "B1") (pin "27") (pinfunction "5V_27") (pintype "bidirectional"))
      (node (ref "D1") (pin "A") (pinfunction "A_A") (pintype "passive"))
      (node (ref "D2") (pin "A") (pinfunction "A_A") (pintype "passive"))
      (node (ref "D3") (pin "A") (pinfunction "A_A") (pintype "passive"))
      (node (ref "D4") (pin "A") (pinfunction "A_A") (pintype "passive"))
      (node (ref "JP1") (pin "12") (pinfunction "12_12") (pintype "passive"))
      (node (ref "R11") (pin "2") (pinfunction "2_2") (pintype "passive"))
      (node (ref "R2") (pin "2") (pinfunction "2_2") (pintype "passive"))
      (node (ref "R5") (pin "2") (pinfunction "2_2") (pintype "passive"))
      (node (ref "R8") (pin "2") (pinfunction "2_2") (pintype "passive"))
    )
  )
)
